# 03_GAP9_CHIP_JTAG_XTALs.net
KiCad netlist of a schematic drawn in Altium Designer
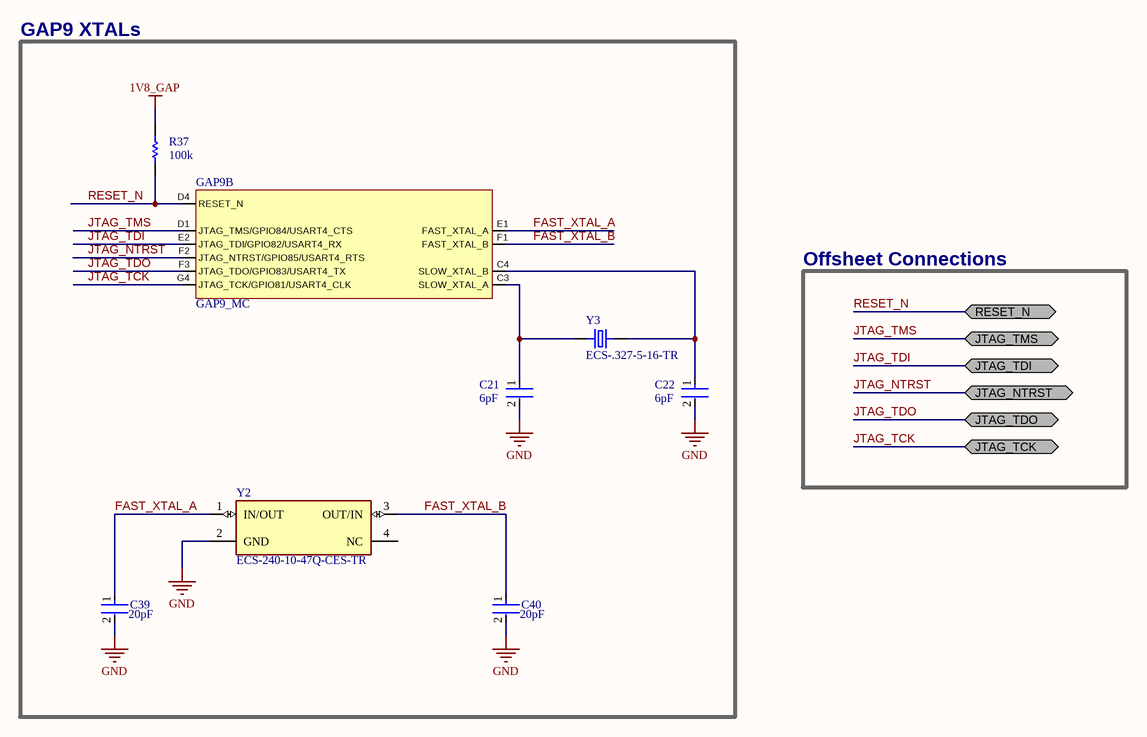
[diagram p0: 03_GAP9_CHIP_JTAG_XTALs.SchDoc]

(export (version "E")
  (design (tool "Eeschema 10.0.6"))
  (components
    (comp (ref "C21")
      (value "6pF")
      (footprint "FP-GJM033-0_03-IPC_A")
      (description "Ceramic Capacitor 6pF ±0.05pF 100V X8G 0201 (0603 Metric)")
      (fields (field (name "Comment") "GJM0335G2A6R0WB01D"))
      (libsource (lib "Altium Content Vault") (part "b4654b650e69147ec39a6b967a45e02"))
    )
    (comp (ref "C22")
      (value "6pF")
      (footprint "FP-GJM033-0_03-IPC_A")
      (description "Ceramic Capacitor 6pF ±0.05pF 100V X8G 0201 (0603 Metric)")
      (fields (field (name "Comment") "GJM0335G2A6R0WB01D"))
      (libsource (lib "Altium Content Vault") (part "b4654b650e69147ec39a6b967a45e02"))
    )
    (comp (ref "C39")
      (value "20pF")
      (footprint "CAPC6333_33N_KEM-L")
      (description "No Description Available")
      (fields
        (field (name "MANUFACTURER_PART_NUMBER") "CBR02C200F5GAC")
        (field (name "COPYRIGHT") "Copyright (C) 2022 Ultra Librarian. All rights reserved.")
      )
      (libsource (lib "EEG_SchLib") (part "CBR02C200F5GAC"))
    )
    (comp (ref "C40")
      (value "20pF")
      (footprint "CAPC6333_33N_KEM-L")
      (description "No Description Available")
      (fields
        (field (name "MANUFACTURER_PART_NUMBER") "CBR02C200F5GAC")
        (field (name "COPYRIGHT") "Copyright (C) 2022 Ultra Librarian. All rights reserved.")
      )
      (libsource (lib "EEG_SchLib") (part "CBR02C200F5GAC"))
    )
    (comp (ref "GAP9")
      (value "GAP9_MC")
      (footprint "EEG_PcbLib:GAP9")
      (libsource (lib "EEG_SchLib") (part "GAP9_MC"))
    )
    (comp (ref "R37")
      (value "ERJ-1GNF1003C")
      (footprint "RESC0201(0603)_N")
      (description "100K 0.05W 1% 0201 (0603 Metric)  SMD")
      (fields
        (field (name "POWER") "0.05 W")
        (field (name "TOLERANCE") "1 %")
        (field (name "RESISTANCE") "100k")
      )
      (libsource (lib "Altium Content Vault") (part "RES"))
    )
    (comp (ref "Y2")
      (value "ECS-240-10-47Q-CES-TR")
      (footprint "XTAL_ECS-240-10-47Q-CES-TR")
      (description "24MHz Â±10ppm Crystal 10pF 150 Ohms 4-SMD, No Lead")
      (fields (field (name "MF") "ECS Inc."))
      (libsource (lib "EEG_SchLib") (part "ECS-240-10-47Q-CES-TR"))
    )
    (comp (ref "Y3")
      (value "ECS-.327-5-16-TR")
      (footprint "XTAL_ECS-.327-5-16-TR")
      (description "32.768kHz Â±20ppm Crystal 9pF 90 kOhms 2-SMD, No Lead")
      (fields (field (name "MF") "ECS Inc.") (field (name "MP") "ECS-.327-9-16-TR"))
      (libsource (lib "EEG_SchLib") (part "ECS-.327-5-16-TR"))
    )
  )
  (nets
    (net (code "1") (name "/FAST_XTAL_A") (class "Default")
      (node (ref "C39") (pin "1") (pinfunction "1_1") (pintype "passive"))
      (node (ref "GAP9") (pin "E1") (pinfunction "FAST_XTAL_A_E1") (pintype "passive"))
      (node (ref "Y2") (pin "1") (pinfunction "IN/OUT_1") (pintype "bidirectional"))
    )
    (net (code "2") (name "/FAST_XTAL_B") (class "Default")
      (node (ref "C40") (pin "1") (pinfunction "1_1") (pintype "passive"))
      (node (ref "GAP9") (pin "F1") (pinfunction "FAST_XTAL_B_F1") (pintype "passive"))
      (node (ref "Y2") (pin "3") (pinfunction "OUT/IN_3") (pintype "bidirectional"))
    )
    (net (code "3") (name "/JTAG_NTRST") (class "Default")
      (node (ref "GAP9") (pin "F2") (pinfunction "JTAG_NTRST/GPIO85/USART4_RTS_F2") (pintype "passive"))
    )
    (net (code "4") (name "/JTAG_TCK") (class "Default")
      (node (ref "GAP9") (pin "G4") (pinfunction "JTAG_TCK/GPIO81/USART4_CLK_G4") (pintype "passive"))
    )
    (net (code "5") (name "/JTAG_TDI") (class "Default")
      (node (ref "GAP9") (pin "E2") (pinfunction "JTAG_TDI/GPIO82/USART4_RX_E2") (pintype "passive"))
    )
    (net (code "6") (name "/JTAG_TDO") (class "Default")
      (node (ref "GAP9") (pin "F3") (pinfunction "JTAG_TDO/GPIO83/USART4_TX_F3") (pintype "passive"))
    )
    (net (code "7") (name "/JTAG_TMS") (class "Default")
      (node (ref "GAP9") (pin "D1") (pinfunction "JTAG_TMS/GPIO84/USART4_CTS_D1") (pintype "passive"))
    )
    (net (code "8") (name "/RESET_N") (class "Default")
      (node (ref "GAP9") (pin "D4") (pinfunction "RESET_N_D4") (pintype "passive"))
      (node (ref "R37") (pin "1") (pinfunction "1_1") (pintype "passive"))
    )
    (net (code "9") (name "1V8_GAP") (class "Default")
      (node (ref "R37") (pin "2") (pinfunction "2_2") (pintype "passive"))
    )
    (net (code "10") (name "GND") (class "Default")
      (node (ref "C21") (pin "2") (pinfunction "2_2") (pintype "passive"))
      (node (ref "C22") (pin "2") (pinfunction "2_2") (pintype "passive"))
      (node (ref "C39") (pin "2") (pinfunction "2_2") (pintype "passive"))
      (node (ref "C40") (pin "2") (pinfunction "2_2") (pintype "passive"))
      (node (ref "Y2") (pin "2") (pinfunction "GND_2") (pintype "passive"))
    )
    (net (code "11") (name "Net-(GAP9B-SLOW_XTAL_A)") (class "Default")
      (node (ref "C21") (pin "1") (pinfunction "1_1") (pintype "passive"))
      (node (ref "GAP9") (pin "C3") (pinfunction "SLOW_XTAL_A_C3") (pintype "passive"))
      (node (ref "Y3") (pin "1") (pinfunction "1_1") (pintype "passive"))
    )
    (net (code "12") (name "Net-(GAP9B-SLOW_XTAL_B)") (class "Default")
      (node (ref "C22") (pin "1") (pinfunction "1_1") (pintype "passive"))
      (node (ref "GAP9") (pin "C4") (pinfunction "SLOW_XTAL_B_C4") (pintype "passive"))
      (node (ref "Y3") (pin "2") (pinfunction "2_2") (pintype "passive"))
    )
    (net (code "13") (name "unconnected-(Y2-NC-Pad4)") (class "Default")
      (node (ref "Y2") (pin "4") (pinfunction "NC_4") (pintype "passive"))
    )
  )
)
